# PCBv2.net
KiCad netlist of a schematic drawn in EAGLE
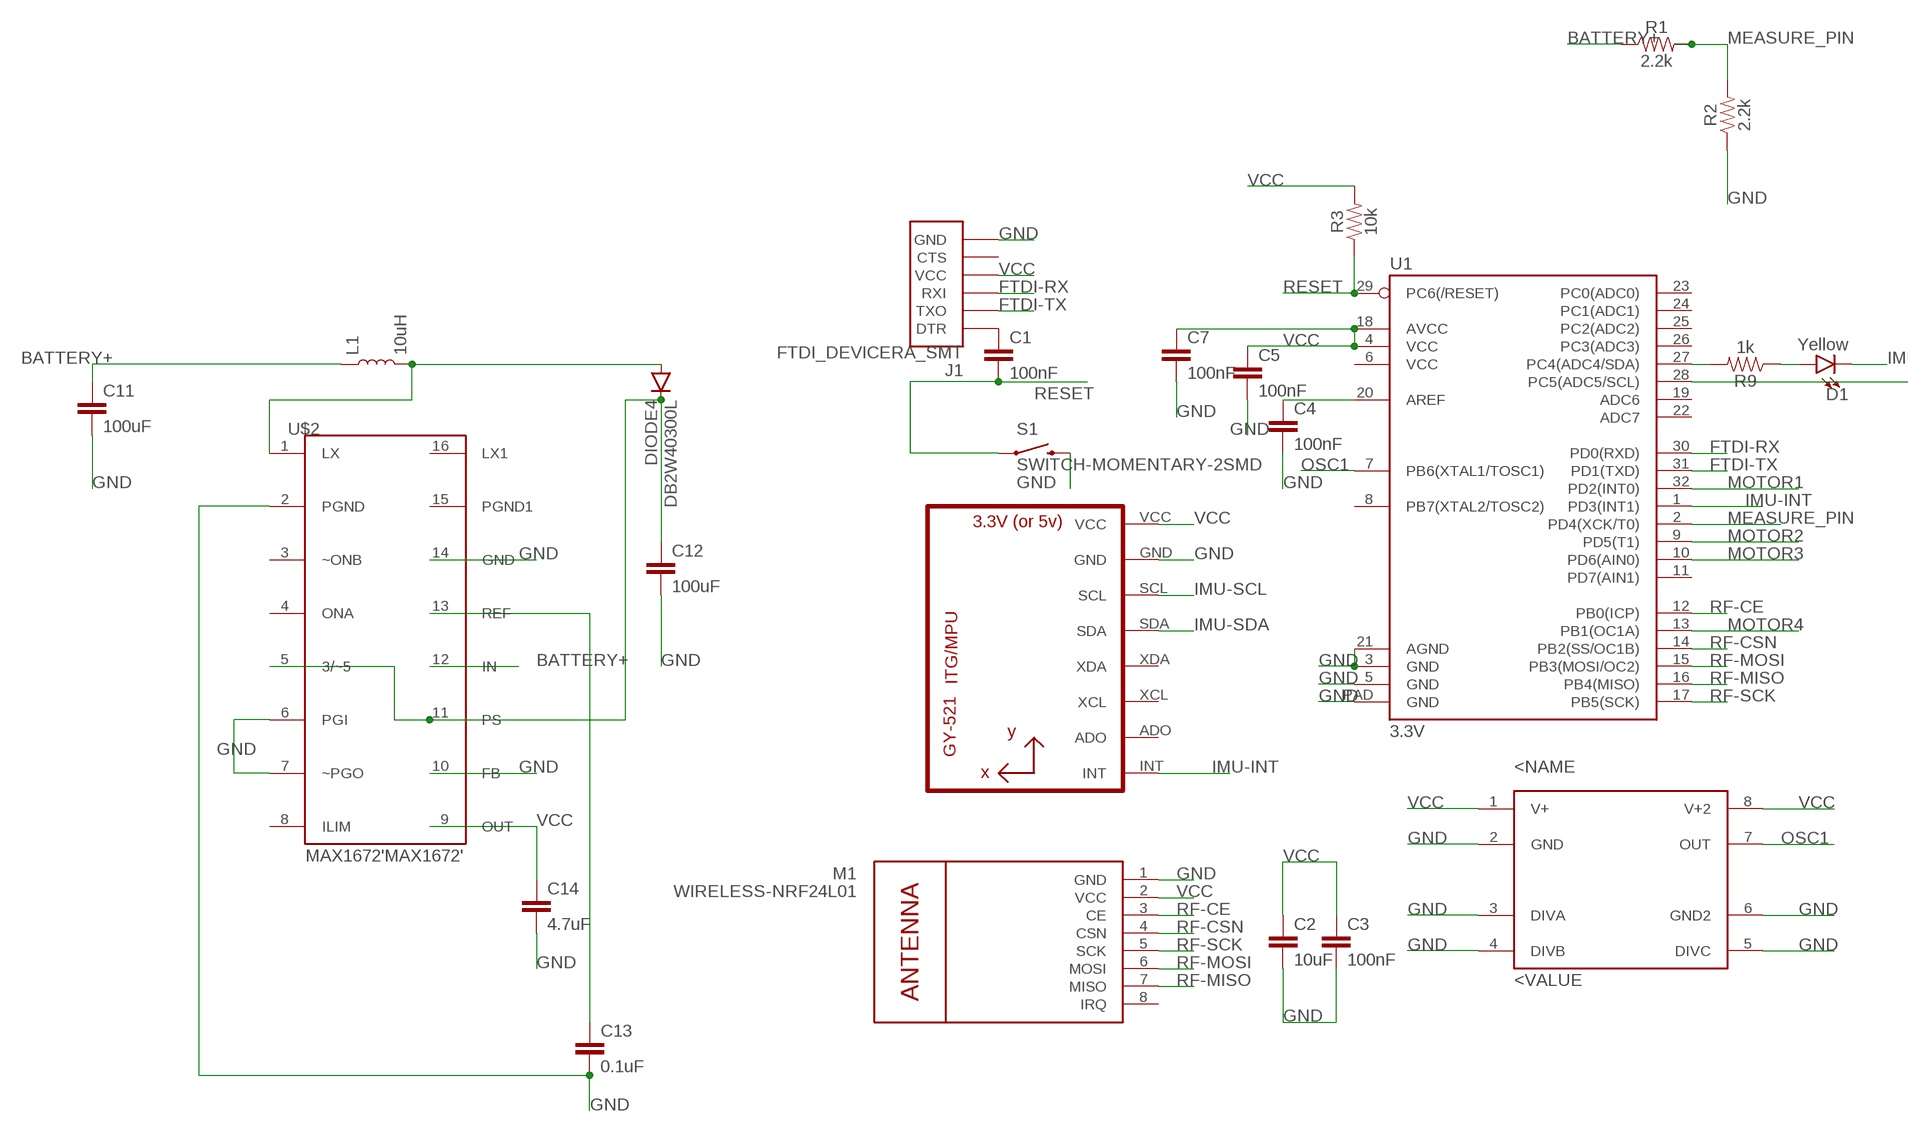
[diagram p0: schematic, sheet 1, part 1 of 2]
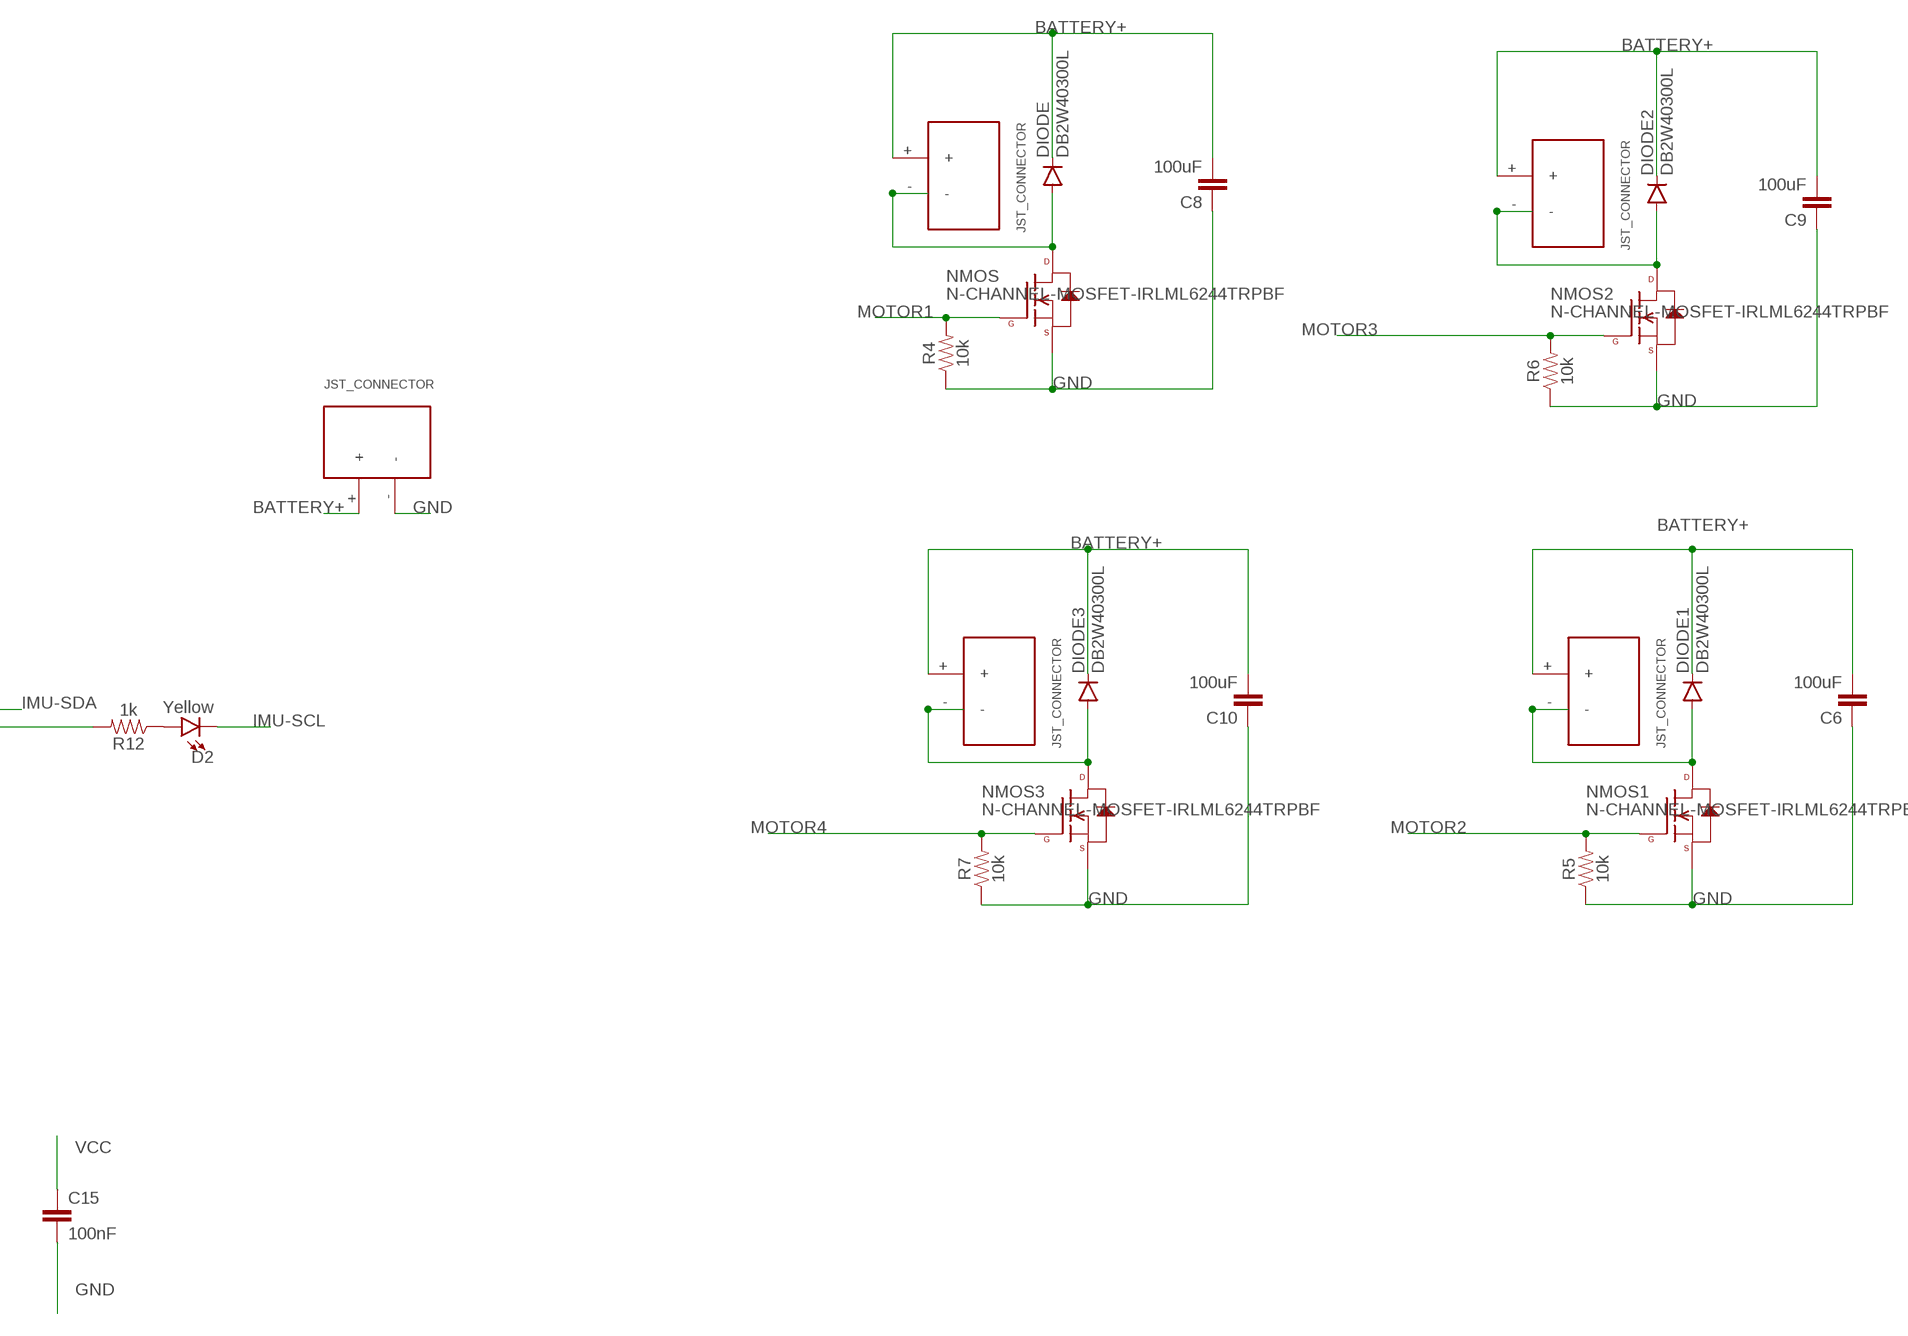
[diagram p1: schematic, sheet 1, part 2 of 2]

(export (version "E")
  (design (tool "Eeschema 10.0.6"))
  (components
    (comp (ref "C1")
      (value "100nF")
      (footprint "eagle-import:0603-CAP")
      (libsource (lib "eagle-import") (part "0.1UF-25V(+80/-20%)(0603)"))
    )
    (comp (ref "C2")
      (value "10uF")
      (footprint "eagle-import:0603-CAP")
      (libsource (lib "eagle-import") (part "CAP0603-CAP"))
    )
    (comp (ref "C3")
      (value "100nF")
      (footprint "eagle-import:0603-CAP")
      (libsource (lib "eagle-import") (part "CAP0603-CAP"))
    )
    (comp (ref "C4")
      (value "100nF")
      (footprint "eagle-import:0603-CAP")
      (libsource (lib "eagle-import") (part "CAP0603-CAP"))
    )
    (comp (ref "C5")
      (value "100nF")
      (footprint "eagle-import:0603-CAP")
      (libsource (lib "eagle-import") (part "CAP0603-CAP"))
    )
    (comp (ref "C6")
      (value "100uF")
      (footprint "eagle-import:0603-CAP")
      (libsource (lib "eagle-import") (part "CAP0603-CAP"))
    )
    (comp (ref "C7")
      (value "100nF")
      (footprint "eagle-import:0603-CAP")
      (libsource (lib "eagle-import") (part "CAP0603-CAP"))
    )
    (comp (ref "C8")
      (value "100uF")
      (footprint "eagle-import:0603-CAP")
      (libsource (lib "eagle-import") (part "CAP0603-CAP"))
    )
    (comp (ref "C9")
      (value "100uF")
      (footprint "eagle-import:0603-CAP")
      (libsource (lib "eagle-import") (part "CAP0603-CAP"))
    )
    (comp (ref "C10")
      (value "100uF")
      (footprint "eagle-import:0603-CAP")
      (libsource (lib "eagle-import") (part "CAP0603-CAP"))
    )
    (comp (ref "C11")
      (value "100uF")
      (footprint "eagle-import:0603-CAP")
      (libsource (lib "eagle-import") (part "CAP0603-CAP"))
    )
    (comp (ref "C12")
      (value "100uF")
      (footprint "eagle-import:0603-CAP")
      (libsource (lib "eagle-import") (part "CAP0603-CAP"))
    )
    (comp (ref "C13")
      (value "0.1uF")
      (footprint "eagle-import:0603-CAP")
      (libsource (lib "eagle-import") (part "CAP0603-CAP"))
    )
    (comp (ref "C14")
      (value "4.7uF")
      (footprint "eagle-import:0603-CAP")
      (libsource (lib "eagle-import") (part "CAP0603-CAP"))
    )
    (comp (ref "C15")
      (value "100nF")
      (footprint "eagle-import:0603-CAP")
      (libsource (lib "eagle-import") (part "0.1UF-25V(+80/-20%)(0603)"))
    )
    (comp (ref "D1")
      (value "Yellow")
      (footprint "eagle-import:LED-1206")
      (libsource (lib "eagle-import") (part "LED-YELLOWLILYPAD"))
    )
    (comp (ref "D2")
      (value "Yellow")
      (footprint "eagle-import:LED-1206")
      (libsource (lib "eagle-import") (part "LED-YELLOWLILYPAD"))
    )
    (comp (ref "DIODE")
      (value "DB2W40300L")
      (footprint "eagle-import:MINI2-F3-B")
      (libsource (lib "eagle-import") (part "DB2W40300L"))
    )
    (comp (ref "DIODE1")
      (value "DB2W40300L")
      (footprint "eagle-import:MINI2-F3-B")
      (libsource (lib "eagle-import") (part "DB2W40300L"))
    )
    (comp (ref "DIODE2")
      (value "DB2W40300L")
      (footprint "eagle-import:MINI2-F3-B")
      (libsource (lib "eagle-import") (part "DB2W40300L"))
    )
    (comp (ref "DIODE3")
      (value "DB2W40300L")
      (footprint "eagle-import:MINI2-F3-B")
      (libsource (lib "eagle-import") (part "DB2W40300L"))
    )
    (comp (ref "DIODE4")
      (value "DB2W40300L")
      (footprint "eagle-import:MINI2-F3-B")
      (libsource (lib "eagle-import") (part "DB2W40300L"))
    )
    (comp (ref "J1")
      (value "FTDI_DEVICERA_SMT")
      (footprint "eagle-import:FTDI_DEVICE_RA_SMT")
      (libsource (lib "eagle-import") (part "FTDI_DEVICERA_SMT"))
    )
    (comp (ref "L1")
      (value "10uH")
      (footprint "eagle-import:0603")
      (libsource (lib "eagle-import") (part "INDUCTOR-0603-33NH"))
    )
    (comp (ref "M1")
      (value "WIRELESS-NRF24L01")
      (footprint "eagle-import:WIRELESS-NRF24L01")
      (libsource (lib "eagle-import") (part "WIRELESS-NRF24L01"))
    )
    (comp (ref "MOTOR")
      (value "JST_CONNECTOR_FEMALE")
      (footprint "eagle-import:JST_CONNECTOR_FEMALE")
      (libsource (lib "eagle-import") (part "JST_CONNECTOR_FEMALE"))
    )
    (comp (ref "MOTOR1")
      (value "JST_CONNECTOR_FEMALE")
      (footprint "eagle-import:JST_CONNECTOR_FEMALE")
      (libsource (lib "eagle-import") (part "JST_CONNECTOR_FEMALE"))
    )
    (comp (ref "MOTOR2")
      (value "JST_CONNECTOR_FEMALE")
      (footprint "eagle-import:JST_CONNECTOR_FEMALE")
      (libsource (lib "eagle-import") (part "JST_CONNECTOR_FEMALE"))
    )
    (comp (ref "MOTOR3")
      (value "JST_CONNECTOR_FEMALE")
      (footprint "eagle-import:JST_CONNECTOR_FEMALE")
      (libsource (lib "eagle-import") (part "JST_CONNECTOR_FEMALE"))
    )
    (comp (ref "NMOS")
      (value "N-CHANNEL-MOSFET-IRLML6244TRPBF")
      (footprint "eagle-import:SOT23-3")
      (libsource (lib "eagle-import") (part "N-CHANNEL-MOSFET-IRLML6244TRPBF"))
    )
    (comp (ref "NMOS1")
      (value "N-CHANNEL-MOSFET-IRLML6244TRPBF")
      (footprint "eagle-import:SOT23-3")
      (libsource (lib "eagle-import") (part "N-CHANNEL-MOSFET-IRLML6244TRPBF"))
    )
    (comp (ref "NMOS2")
      (value "N-CHANNEL-MOSFET-IRLML6244TRPBF")
      (footprint "eagle-import:SOT23-3")
      (libsource (lib "eagle-import") (part "N-CHANNEL-MOSFET-IRLML6244TRPBF"))
    )
    (comp (ref "NMOS3")
      (value "N-CHANNEL-MOSFET-IRLML6244TRPBF")
      (footprint "eagle-import:SOT23-3")
      (libsource (lib "eagle-import") (part "N-CHANNEL-MOSFET-IRLML6244TRPBF"))
    )
    (comp (ref "R1")
      (value "2.2k")
      (footprint "eagle-import:0603")
      (libsource (lib "eagle-import") (part "2.2KOHM-0603-1/10W-1%"))
    )
    (comp (ref "R2")
      (value "2.2k")
      (footprint "eagle-import:0603")
      (libsource (lib "eagle-import") (part "2.2KOHM-0603-1/10W-1%"))
    )
    (comp (ref "R3")
      (value "10k")
      (footprint "eagle-import:0603")
      (libsource (lib "eagle-import") (part "2.2KOHM-0603-1/10W-1%"))
    )
    (comp (ref "R4")
      (value "10k")
      (footprint "eagle-import:0603")
      (libsource (lib "eagle-import") (part "2.2KOHM-0603-1/10W-1%"))
    )
    (comp (ref "R5")
      (value "10k")
      (footprint "eagle-import:0603")
      (libsource (lib "eagle-import") (part "2.2KOHM-0603-1/10W-1%"))
    )
    (comp (ref "R6")
      (value "10k")
      (footprint "eagle-import:0603")
      (libsource (lib "eagle-import") (part "2.2KOHM-0603-1/10W-1%"))
    )
    (comp (ref "R7")
      (value "10k")
      (footprint "eagle-import:0603")
      (libsource (lib "eagle-import") (part "2.2KOHM-0603-1/10W-1%"))
    )
    (comp (ref "R9")
      (value "1k")
      (footprint "eagle-import:0603")
      (libsource (lib "eagle-import") (part "2.2KOHM-0603-1/10W-1%"))
    )
    (comp (ref "R12")
      (value "1k")
      (footprint "eagle-import:0603")
      (libsource (lib "eagle-import") (part "2.2KOHM-0603-1/10W-1%"))
    )
    (comp (ref "S1")
      (value "SWITCH-MOMENTARY-2SMD")
      (footprint "eagle-import:TACTILE-SWITCH-SMD")
      (libsource (lib "eagle-import") (part "SWITCH-MOMENTARY-2SMD"))
    )
    (comp (ref "U$1")
      (value "JST_CONNECTOR_FEMALE")
      (footprint "eagle-import:JST_CONNECTOR_FEMALE")
      (libsource (lib "eagle-import") (part "JST_CONNECTOR_FEMALE"))
    )
    (comp (ref "U$2")
      (value "MAX1672'MAX1672'")
      (footprint "eagle-import:21-0055H_16")
      (libsource (lib "eagle-import") (part "MAX1672'MAX1672'"))
    )
    (comp (ref "U$3")
      (value "LTC6930CMS8-8.19LTC6930CMS8-8.19")
      (footprint "eagle-import:SOP65P490X110-8N")
      (libsource (lib "eagle-import") (part "LTC6930CMS8-8.19LTC6930CMS8-8.19"))
    )
    (comp (ref "U1")
      (value "3.3V")
      (footprint "eagle-import:MLF32-PAD")
      (libsource (lib "eagle-import") (part "ATMEGA328P_MLFMLF32"))
    )
    (comp (ref "U2")
      (value "GY-521MPU6050")
      (footprint "eagle-import:GY-521")
      (libsource (lib "eagle-import") (part "GY-521MPU6050"))
    )
  )
  (nets
    (net (code "1") (name "BATTERY+") (class "Default")
      (node (ref "C10") (pin "2") (pinfunction "2_2") (pintype "passive"))
      (node (ref "C11") (pin "1") (pinfunction "1_1") (pintype "passive"))
      (node (ref "C6") (pin "2") (pinfunction "2_2") (pintype "passive"))
      (node (ref "C8") (pin "2") (pinfunction "2_2") (pintype "passive"))
      (node (ref "C9") (pin "2") (pinfunction "2_2") (pintype "passive"))
      (node (ref "DIODE") (pin "NEG") (pinfunction "GPIN_NEG") (pintype "passive"))
      (node (ref "DIODE1") (pin "NEG") (pinfunction "GPIN_NEG") (pintype "passive"))
      (node (ref "DIODE2") (pin "NEG") (pinfunction "GPIN_NEG") (pintype "passive"))
      (node (ref "DIODE3") (pin "NEG") (pinfunction "GPIN_NEG") (pintype "passive"))
      (node (ref "L1") (pin "1") (pinfunction "1_1") (pintype "passive"))
      (node (ref "MOTOR") (pin "+") (pinfunction "+_+") (pintype "bidirectional"))
      (node (ref "MOTOR1") (pin "+") (pinfunction "+_+") (pintype "bidirectional"))
      (node (ref "MOTOR2") (pin "+") (pinfunction "+_+") (pintype "bidirectional"))
      (node (ref "MOTOR3") (pin "+") (pinfunction "+_+") (pintype "bidirectional"))
      (node (ref "R1") (pin "1") (pinfunction "1_1") (pintype "passive"))
      (node (ref "U$1") (pin "+") (pinfunction "+_+") (pintype "bidirectional"))
      (node (ref "U$2") (pin "12") (pinfunction "IN_12") (pintype "bidirectional"))
    )
    (net (code "2") (name "FTDI-RX") (class "Default")
      (node (ref "J1") (pin "3") (pinfunction "RXI_3") (pintype "bidirectional"))
      (node (ref "U1") (pin "30") (pinfunction "PD0(RXD)_30") (pintype "bidirectional"))
    )
    (net (code "3") (name "FTDI-TX") (class "Default")
      (node (ref "J1") (pin "2") (pinfunction "TXO_2") (pintype "bidirectional"))
      (node (ref "U1") (pin "31") (pinfunction "PD1(TXD)_31") (pintype "bidirectional"))
    )
    (net (code "4") (name "GND") (class "Default")
      (node (ref "C10") (pin "1") (pinfunction "1_1") (pintype "passive"))
      (node (ref "C11") (pin "2") (pinfunction "2_2") (pintype "passive"))
      (node (ref "C12") (pin "2") (pinfunction "2_2") (pintype "passive"))
      (node (ref "C13") (pin "2") (pinfunction "2_2") (pintype "passive"))
      (node (ref "C14") (pin "2") (pinfunction "2_2") (pintype "passive"))
      (node (ref "C15") (pin "2") (pinfunction "2_2") (pintype "passive"))
      (node (ref "C2") (pin "2") (pinfunction "2_2") (pintype "passive"))
      (node (ref "C3") (pin "2") (pinfunction "2_2") (pintype "passive"))
      (node (ref "C4") (pin "2") (pinfunction "2_2") (pintype "passive"))
      (node (ref "C5") (pin "2") (pinfunction "2_2") (pintype "passive"))
      (node (ref "C6") (pin "1") (pinfunction "1_1") (pintype "passive"))
      (node (ref "C7") (pin "2") (pinfunction "2_2") (pintype "passive"))
      (node (ref "C8") (pin "1") (pinfunction "1_1") (pintype "passive"))
      (node (ref "C9") (pin "1") (pinfunction "1_1") (pintype "passive"))
      (node (ref "J1") (pin "6") (pinfunction "GND_6") (pintype "bidirectional"))
      (node (ref "M1") (pin "1") (pinfunction "GND_1") (pintype "power_in"))
      (node (ref "NMOS") (pin "2") (pinfunction "S_2") (pintype "passive"))
      (node (ref "NMOS1") (pin "2") (pinfunction "S_2") (pintype "passive"))
      (node (ref "NMOS2") (pin "2") (pinfunction "S_2") (pintype "passive"))
      (node (ref "NMOS3") (pin "2") (pinfunction "S_2") (pintype "passive"))
      (node (ref "R2") (pin "1") (pinfunction "1_1") (pintype "passive"))
      (node (ref "R4") (pin "1") (pinfunction "1_1") (pintype "passive"))
      (node (ref "R5") (pin "1") (pinfunction "1_1") (pintype "passive"))
      (node (ref "R6") (pin "1") (pinfunction "1_1") (pintype "passive"))
      (node (ref "R7") (pin "1") (pinfunction "1_1") (pintype "passive"))
      (node (ref "S1") (pin "3") (pinfunction "2_3") (pintype "passive"))
      (node (ref "U$1") (pin "-") (pinfunction "-_-") (pintype "bidirectional"))
      (node (ref "U$2") (pin "10") (pinfunction "FB_10") (pintype "bidirectional"))
      (node (ref "U$2") (pin "14") (pinfunction "GND_14") (pintype "bidirectional"))
      (node (ref "U$2") (pin "2") (pinfunction "PGND_2") (pintype "bidirectional"))
      (node (ref "U$2") (pin "6") (pinfunction "PGI_6") (pintype "bidirectional"))
      (node (ref "U$2") (pin "7") (pinfunction "~{PGO}_7") (pintype "bidirectional"))
      (node (ref "U$3") (pin "2") (pinfunction "GND_2") (pintype "bidirectional"))
      (node (ref "U$3") (pin "3") (pinfunction "DIVA_3") (pintype "bidirectional"))
      (node (ref "U$3") (pin "4") (pinfunction "DIVB_4") (pintype "bidirectional"))
      (node (ref "U$3") (pin "5") (pinfunction "DIVC_5") (pintype "bidirectional"))
      (node (ref "U$3") (pin "6") (pinfunction "GND2_6") (pintype "bidirectional"))
      (node (ref "U1") (pin "21") (pinfunction "AGND_21") (pintype "bidirectional"))
      (node (ref "U1") (pin "3") (pinfunction "GND_3") (pintype "bidirectional"))
      (node (ref "U1") (pin "5") (pinfunction "GND_5") (pintype "bidirectional"))
      (node (ref "U1") (pin "PAD") (pinfunction "GND_PAD") (pintype "bidirectional"))
      (node (ref "U2") (pin "GND") (pinfunction "GND_GND") (pintype "bidirectional"))
    )
    (net (code "5") (name "IMU-INT") (class "Default")
      (node (ref "U1") (pin "1") (pinfunction "PD3(INT1)_1") (pintype "bidirectional"))
      (node (ref "U2") (pin "INT") (pinfunction "INT_INT") (pintype "bidirectional"))
    )
    (net (code "6") (name "IMU-SCL") (class "Default")
      (node (ref "D2") (pin "C") (pinfunction "C_C") (pintype "passive"))
      (node (ref "U2") (pin "SCL") (pinfunction "SCL_SCL") (pintype "bidirectional"))
    )
    (net (code "7") (name "IMU-SDA") (class "Default")
      (node (ref "D1") (pin "C") (pinfunction "C_C") (pintype "passive"))
      (node (ref "U2") (pin "SDA") (pinfunction "SDA_SDA") (pintype "bidirectional"))
    )
    (net (code "8") (name "MEASURE_PIN") (class "Default")
      (node (ref "R1") (pin "2") (pinfunction "2_2") (pintype "passive"))
      (node (ref "R2") (pin "2") (pinfunction "2_2") (pintype "passive"))
      (node (ref "U1") (pin "2") (pinfunction "PD4(XCK/T0)_2") (pintype "bidirectional"))
    )
    (net (code "9") (name "MOTOR1") (class "Default")
      (node (ref "NMOS") (pin "1") (pinfunction "G_1") (pintype "passive"))
      (node (ref "R4") (pin "2") (pinfunction "2_2") (pintype "passive"))
      (node (ref "U1") (pin "32") (pinfunction "PD2(INT0)_32") (pintype "bidirectional"))
    )
    (net (code "10") (name "MOTOR2") (class "Default")
      (node (ref "NMOS1") (pin "1") (pinfunction "G_1") (pintype "passive"))
      (node (ref "R5") (pin "2") (pinfunction "2_2") (pintype "passive"))
      (node (ref "U1") (pin "9") (pinfunction "PD5(T1)_9") (pintype "bidirectional"))
    )
    (net (code "11") (name "MOTOR3") (class "Default")
      (node (ref "NMOS2") (pin "1") (pinfunction "G_1") (pintype "passive"))
      (node (ref "R6") (pin "2") (pinfunction "2_2") (pintype "passive"))
      (node (ref "U1") (pin "10") (pinfunction "PD6(AIN0)_10") (pintype "bidirectional"))
    )
    (net (code "12") (name "MOTOR4") (class "Default")
      (node (ref "NMOS3") (pin "1") (pinfunction "G_1") (pintype "passive"))
      (node (ref "R7") (pin "2") (pinfunction "2_2") (pintype "passive"))
      (node (ref "U1") (pin "13") (pinfunction "PB1(OC1A)_13") (pintype "bidirectional"))
    )
    (net (code "13") (name "Net-(D1-PadA)") (class "Default")
      (node (ref "D1") (pin "A") (pinfunction "A_A") (pintype "passive"))
      (node (ref "R9") (pin "1") (pinfunction "1_1") (pintype "passive"))
    )
    (net (code "14") (name "Net-(D2-PadA)") (class "Default")
      (node (ref "D2") (pin "A") (pinfunction "A_A") (pintype "passive"))
      (node (ref "R12") (pin "1") (pinfunction "1_1") (pintype "passive"))
    )
    (net (code "15") (name "Net-(DIODE-PPIN)") (class "Default")
      (node (ref "DIODE") (pin "POS") (pinfunction "PPIN_POS") (pintype "passive"))
      (node (ref "MOTOR") (pin "-") (pinfunction "-_-") (pintype "bidirectional"))
      (node (ref "NMOS") (pin "3") (pinfunction "D_3") (pintype "passive"))
    )
    (net (code "16") (name "Net-(DIODE1-PPIN)") (class "Default")
      (node (ref "DIODE1") (pin "POS") (pinfunction "PPIN_POS") (pintype "passive"))
      (node (ref "MOTOR1") (pin "-") (pinfunction "-_-") (pintype "bidirectional"))
      (node (ref "NMOS1") (pin "3") (pinfunction "D_3") (pintype "passive"))
    )
    (net (code "17") (name "Net-(DIODE2-PPIN)") (class "Default")
      (node (ref "DIODE2") (pin "POS") (pinfunction "PPIN_POS") (pintype "passive"))
      (node (ref "MOTOR2") (pin "-") (pinfunction "-_-") (pintype "bidirectional"))
      (node (ref "NMOS2") (pin "3") (pinfunction "D_3") (pintype "passive"))
    )
    (net (code "18") (name "Net-(DIODE3-PPIN)") (class "Default")
      (node (ref "DIODE3") (pin "POS") (pinfunction "PPIN_POS") (pintype "passive"))
      (node (ref "MOTOR3") (pin "-") (pinfunction "-_-") (pintype "bidirectional"))
      (node (ref "NMOS3") (pin "3") (pinfunction "D_3") (pintype "passive"))
    )
    (net (code "19") (name "Net-(DIODE4-GPIN)") (class "Default")
      (node (ref "C12") (pin "1") (pinfunction "1_1") (pintype "passive"))
      (node (ref "DIODE4") (pin "NEG") (pinfunction "GPIN_NEG") (pintype "passive"))
      (node (ref "U$2") (pin "11") (pinfunction "PS_11") (pintype "bidirectional"))
      (node (ref "U$2") (pin "5") (pinfunction "3/~{5}_5") (pintype "bidirectional"))
    )
    (net (code "20") (name "Net-(DIODE4-PPIN)") (class "Default")
      (node (ref "DIODE4") (pin "POS") (pinfunction "PPIN_POS") (pintype "passive"))
      (node (ref "L1") (pin "2") (pinfunction "2_2") (pintype "passive"))
      (node (ref "U$2") (pin "1") (pinfunction "LX_1") (pintype "bidirectional"))
    )
    (net (code "21") (name "Net-(J1-DTR)") (class "Default")
      (node (ref "C1") (pin "1") (pinfunction "1_1") (pintype "passive"))
      (node (ref "J1") (pin "1") (pinfunction "DTR_1") (pintype "bidirectional"))
    )
    (net (code "22") (name "Net-(U$2-REF)") (class "Default")
      (node (ref "C13") (pin "1") (pinfunction "1_1") (pintype "passive"))
      (node (ref "U$2") (pin "13") (pinfunction "REF_13") (pintype "bidirectional"))
    )
    (net (code "23") (name "Net-(U1-AREF)") (class "Default")
      (node (ref "C4") (pin "1") (pinfunction "1_1") (pintype "passive"))
      (node (ref "U1") (pin "20") (pinfunction "AREF_20") (pintype "bidirectional"))
    )
    (net (code "24") (name "Net-(U1-PC4(ADC4{slash}SDA))") (class "Default")
      (node (ref "R9") (pin "2") (pinfunction "2_2") (pintype "passive"))
      (node (ref "U1") (pin "27") (pinfunction "PC4(ADC4/SDA)_27") (pintype "bidirectional"))
    )
    (net (code "25") (name "Net-(U1-PC5(ADC5{slash}SCL))") (class "Default")
      (node (ref "R12") (pin "2") (pinfunction "2_2") (pintype "passive"))
      (node (ref "U1") (pin "28") (pinfunction "PC5(ADC5/SCL)_28") (pintype "bidirectional"))
    )
    (net (code "26") (name "OSC1") (class "Default")
      (node (ref "U$3") (pin "7") (pinfunction "OUT_7") (pintype "bidirectional"))
      (node (ref "U1") (pin "7") (pinfunction "PB6(XTAL1/TOSC1)_7") (pintype "bidirectional"))
    )
    (net (code "27") (name "RESET") (class "Default")
      (node (ref "C1") (pin "2") (pinfunction "2_2") (pintype "passive"))
      (node (ref "R3") (pin "1") (pinfunction "1_1") (pintype "passive"))
      (node (ref "S1") (pin "1") (pinfunction "1_1") (pintype "passive"))
      (node (ref "U1") (pin "29") (pinfunction "PC6(/RESET)_29") (pintype "bidirectional"))
    )
    (net (code "28") (name "RF-CE") (class "Default")
      (node (ref "M1") (pin "3") (pinfunction "CE_3") (pintype "bidirectional"))
      (node (ref "U1") (pin "12") (pinfunction "PB0(ICP)_12") (pintype "bidirectional"))
    )
    (net (code "29") (name "RF-CSN") (class "Default")
      (node (ref "M1") (pin "4") (pinfunction "CSN_4") (pintype "bidirectional"))
      (node (ref "U1") (pin "14") (pinfunction "PB2(SS/OC1B)_14") (pintype "bidirectional"))
    )
    (net (code "30") (name "RF-MISO") (class "Default")
      (node (ref "M1") (pin "7") (pinfunction "MISO_7") (pintype "bidirectional"))
      (node (ref "U1") (pin "16") (pinfunction "PB4(MISO)_16") (pintype "bidirectional"))
    )
    (net (code "31") (name "RF-MOSI") (class "Default")
      (node (ref "M1") (pin "6") (pinfunction "MOSI_6") (pintype "bidirectional"))
      (node (ref "U1") (pin "15") (pinfunction "PB3(MOSI/OC2)_15") (pintype "bidirectional"))
    )
    (net (code "32") (name "RF-SCK") (class "Default")
      (node (ref "M1") (pin "5") (pinfunction "SCK_5") (pintype "bidirectional"))
      (node (ref "U1") (pin "17") (pinfunction "PB5(SCK)_17") (pintype "bidirectional"))
    )
    (net (code "33") (name "VCC") (class "Default")
      (node (ref "C14") (pin "1") (pinfunction "1_1") (pintype "passive"))
      (node (ref "C15") (pin "1") (pinfunction "1_1") (pintype "passive"))
      (node (ref "C2") (pin "1") (pinfunction "1_1") (pintype "passive"))
      (node (ref "C3") (pin "1") (pinfunction "1_1") (pintype "passive"))
      (node (ref "C5") (pin "1") (pinfunction "1_1") (pintype "passive"))
      (node (ref "C7") (pin "1") (pinfunction "1_1") (pintype "passive"))
      (node (ref "J1") (pin "4") (pinfunction "VCC_4") (pintype "bidirectional"))
      (node (ref "M1") (pin "2") (pinfunction "VCC_2") (pintype "power_in"))
      (node (ref "R3") (pin "2") (pinfunction "2_2") (pintype "passive"))
      (node (ref "U$2") (pin "9") (pinfunction "OUT_9") (pintype "bidirectional"))
      (node (ref "U$3") (pin "1") (pinfunction "V+_1") (pintype "bidirectional"))
      (node (ref "U$3") (pin "8") (pinfunction "V+2_8") (pintype "bidirectional"))
      (node (ref "U1") (pin "18") (pinfunction "AVCC_18") (pintype "bidirectional"))
      (node (ref "U1") (pin "4") (pinfunction "VCC_4") (pintype "bidirectional"))
      (node (ref "U2") (pin "VCC") (pinfunction "VCC_VCC") (pintype "bidirectional"))
    )
    (net (code "34") (name "unconnected-(J1-CTS-Pad5)") (class "Default")
      (node (ref "J1") (pin "5") (pinfunction "CTS_5") (pintype "bidirectional"))
    )
    (net (code "35") (name "unconnected-(M1-IRQ-Pad8)") (class "Default")
      (node (ref "M1") (pin "8") (pinfunction "IRQ_8") (pintype "bidirectional"))
    )
    (net (code "36") (name "unconnected-(U$2-ILIM-Pad8)") (class "Default")
      (node (ref "U$2") (pin "8") (pinfunction "ILIM_8") (pintype "bidirectional"))
    )
    (net (code "37") (name "unconnected-(U$2-LX1-Pad16)") (class "Default")
      (node (ref "U$2") (pin "16") (pinfunction "LX1_16") (pintype "bidirectional"))
    )
    (net (code "38") (name "unconnected-(U$2-ONA-Pad4)") (class "Default")
      (node (ref "U$2") (pin "4") (pinfunction "ONA_4") (pintype "bidirectional"))
    )
    (net (code "39") (name "unconnected-(U$2-PGND1-Pad15)") (class "Default")
      (node (ref "U$2") (pin "15") (pinfunction "PGND1_15") (pintype "bidirectional"))
    )
    (net (code "40") (name "unconnected-(U$2-~{ONB}-Pad3)") (class "Default")
      (node (ref "U$2") (pin "3") (pinfunction "~{ONB}_3") (pintype "bidirectional"))
    )
    (net (code "41") (name "unconnected-(U1-ADC6-Pad19)") (class "Default")
      (node (ref "U1") (pin "19") (pinfunction "ADC6_19") (pintype "bidirectional"))
    )
    (net (code "42") (name "unconnected-(U1-ADC7-Pad22)") (class "Default")
      (node (ref "U1") (pin "22") (pinfunction "ADC7_22") (pintype "bidirectional"))
    )
    (net (code "43") (name "unconnected-(U1-PB7(XTAL2{slash}TOSC2)-Pad8)") (class "Default")
      (node (ref "U1") (pin "8") (pinfunction "PB7(XTAL2/TOSC2)_8") (pintype "bidirectional"))
    )
    (net (code "44") (name "unconnected-(U1-PC0(ADC0)-Pad23)") (class "Default")
      (node (ref "U1") (pin "23") (pinfunction "PC0(ADC0)_23") (pintype "bidirectional"))
    )
    (net (code "45") (name "unconnected-(U1-PC1(ADC1)-Pad24)") (class "Default")
      (node (ref "U1") (pin "24") (pinfunction "PC1(ADC1)_24") (pintype "bidirectional"))
    )
    (net (code "46") (name "unconnected-(U1-PC2(ADC2)-Pad25)") (class "Default")
      (node (ref "U1") (pin "25") (pinfunction "PC2(ADC2)_25") (pintype "bidirectional"))
    )
    (net (code "47") (name "unconnected-(U1-PC3(ADC3)-Pad26)") (class "Default")
      (node (ref "U1") (pin "26") (pinfunction "PC3(ADC3)_26") (pintype "bidirectional"))
    )
    (net (code "48") (name "unconnected-(U1-PD7(AIN1)-Pad11)") (class "Default")
      (node (ref "U1") (pin "11") (pinfunction "PD7(AIN1)_11") (pintype "bidirectional"))
    )
    (net (code "49") (name "unconnected-(U1-VCC-Pad6)") (class "Default")
      (node (ref "U1") (pin "6") (pinfunction "VCC_6") (pintype "bidirectional"))
    )
    (net (code "50") (name "unconnected-(U2-PadADO)") (class "Default")
      (node (ref "U2") (pin "ADO") (pinfunction "ADO_ADO") (pintype "bidirectional"))
    )
    (net (code "51") (name "unconnected-(U2-PadXCL)") (class "Default")
      (node (ref "U2") (pin "XCL") (pinfunction "XCL_XCL") (pintype "bidirectional"))
    )
    (net (code "52") (name "unconnected-(U2-PadXDA)") (class "Default")
      (node (ref "U2") (pin "XDA") (pinfunction "XDA_XDA") (pintype "bidirectional"))
    )
  )
)
